# CAN2XG.net
KiCad netlist of a schematic drawn in Altium Designer
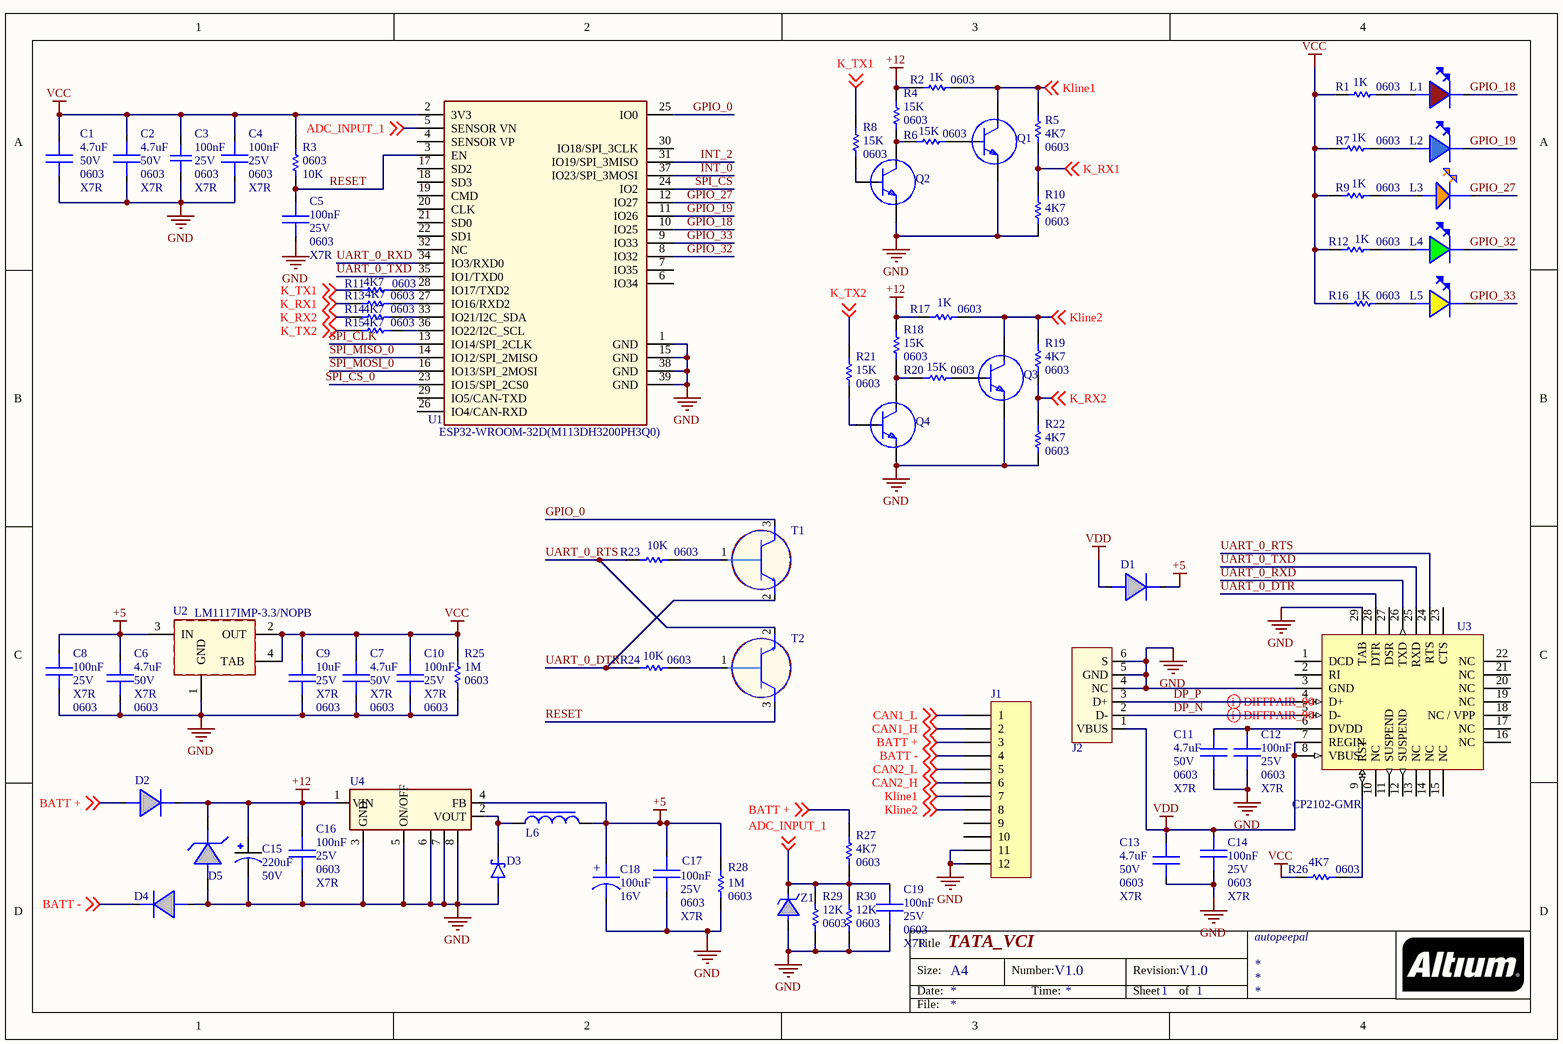
[diagram p0: CAN2XG.SchDoc]

(export (version "E")
  (design (tool "Eeschema 10.0.6"))
  (components
    (comp (ref "C1")
      (value "4.7uF")
      (footprint "CAP-0603")
      (description "CAP CER 4.7uF 50V X7R 0603")
      (fields
        (field (name "VOLTAGE") "50V")
        (field (name "CASE/PACKAGE") "0603")
        (field (name "DIELECTRIC") "X7R")
      )
      (libsource (lib "MyLib") (part "C4.7uF 0603"))
    )
    (comp (ref "C2")
      (value "4.7uF")
      (footprint "CAP-0603")
      (description "CAP CER 4.7uF 50V X7R 0603")
      (fields
        (field (name "VOLTAGE") "50V")
        (field (name "CASE/PACKAGE") "0603")
        (field (name "DIELECTRIC") "X7R")
      )
      (libsource (lib "MyLib") (part "C4.7uF 0603"))
    )
    (comp (ref "C3")
      (value "100nF")
      (footprint "CAP-0603")
      (description "CAP CER 100nF 25V X7R 0603")
      (fields
        (field (name "DIELECTRIC") "X7R")
        (field (name "CASE/PACKAGE") "0603")
        (field (name "VOLTAGE") "25V")
      )
      (libsource (lib "MyLib") (part "C1uF 0603"))
    )
    (comp (ref "C4")
      (value "100nF")
      (footprint "CAP-0603")
      (description "CAP CER 100nF 25V X7R 0603")
      (fields
        (field (name "DIELECTRIC") "X7R")
        (field (name "CASE/PACKAGE") "0603")
        (field (name "VOLTAGE") "25V")
      )
      (libsource (lib "MyLib") (part "C100nF 0603"))
    )
    (comp (ref "C5")
      (value "100nF")
      (footprint "CAP-0603")
      (description "CAP CER 100nF 25V X7R 0603")
      (fields
        (field (name "VOLTAGE") "25V")
        (field (name "CASE/PACKAGE") "0603")
        (field (name "DIELECTRIC") "X7R")
      )
      (libsource (lib "") (part "C1uF 0603_1"))
    )
    (comp (ref "C6")
      (value "4.7uF")
      (footprint "CAP-0603")
      (description "CAP CER 4.7uF 50V X7R 0603")
      (fields
        (field (name "VOLTAGE") "50V")
        (field (name "CASE/PACKAGE") "0603")
        (field (name "DIELECTRIC") "X7R")
      )
      (libsource (lib "MyLib") (part "C4.7uF 0603"))
    )
    (comp (ref "C7")
      (value "4.7uF")
      (footprint "CAP-0603")
      (description "CAP CER 4.7uF 50V X7R 0603")
      (fields
        (field (name "VOLTAGE") "50V")
        (field (name "CASE/PACKAGE") "0603")
        (field (name "DIELECTRIC") "X7R")
      )
      (libsource (lib "MyLib") (part "C4.7uF 0603"))
    )
    (comp (ref "C8")
      (value "100nF")
      (footprint "CAP-0603")
      (description "CAP CER 100nF 25V X7R 0603")
      (fields
        (field (name "VOLTAGE") "25V")
        (field (name "DIELECTRIC") "X7R")
        (field (name "CASE/PACKAGE") "0603")
      )
      (libsource (lib "MyLib") (part "C100nF 0603"))
    )
    (comp (ref "C9")
      (value "10uF")
      (footprint "CAP-0603")
      (description "CAP CER 10uF 25V  0603")
      (fields
        (field (name "VOLTAGE") "25V")
        (field (name "CASE/PACKAGE") "0603")
        (field (name "DIELECTRIC") "X7R")
      )
      (libsource (lib "MyLib") (part "C10uF  0603"))
    )
    (comp (ref "C10")
      (value "100nF")
      (footprint "CAP-0603")
      (description "CAP CER 100nF 25V X7R 0603")
      (fields
        (field (name "CASE/PACKAGE") "0603")
        (field (name "DIELECTRIC") "X7R")
        (field (name "VOLTAGE") "25V")
      )
      (libsource (lib "MyLib") (part "C100nF 0603"))
    )
    (comp (ref "C11")
      (value "4.7uF")
      (footprint "CAP-0603")
      (description "CAP CER 4.7uF 50V X7R 0603")
      (fields
        (field (name "VOLTAGE") "50V")
        (field (name "CASE/PACKAGE") "0603")
        (field (name "DIELECTRIC") "X7R")
      )
      (libsource (lib "MyLib") (part "C4.7uF 0603"))
    )
    (comp (ref "C12")
      (value "100nF")
      (footprint "CAP-0603")
      (description "CAP CER 100nF 25V X7R 0603")
      (fields
        (field (name "VOLTAGE") "25V")
        (field (name "CASE/PACKAGE") "0603")
        (field (name "DIELECTRIC") "X7R")
      )
      (libsource (lib "MyLib") (part "C100nF 0603"))
    )
    (comp (ref "C13")
      (value "4.7uF")
      (footprint "CAP-0603")
      (description "CAP CER 4.7uF 50V X7R 0603")
      (fields
        (field (name "VOLTAGE") "50V")
        (field (name "CASE/PACKAGE") "0603")
        (field (name "DIELECTRIC") "X7R")
      )
      (libsource (lib "MyLib") (part "C4.7uF 0603"))
    )
    (comp (ref "C14")
      (value "100nF")
      (footprint "CAP-0603")
      (description "CAP CER 100nF 25V X7R 0603")
      (fields
        (field (name "VOLTAGE") "25V")
        (field (name "CASE/PACKAGE") "0603")
        (field (name "DIELECTRIC") "X7R")
      )
      (libsource (lib "MyLib") (part "C100nF 0603"))
    )
    (comp (ref "C15")
      (value "220uF")
      (footprint "C200uF 10x10.2")
      (description "220uF 50V 10x10.5mm SMD Electrolytic Capacitor")
      (fields (field (name "VOLTAGE") "50V"))
      (libsource (lib "FotaxLite") (part "C200uF 10x10.2"))
    )
    (comp (ref "C16")
      (value "100nF")
      (footprint "CAP-0603")
      (description "CAP CER 100nF 25V X7R 0603")
      (fields
        (field (name "VOLTAGE") "25V")
        (field (name "CASE/PACKAGE") "0603")
        (field (name "DIELECTRIC") "X7R")
      )
      (libsource (lib "MyLib") (part "C100nF 0603"))
    )
    (comp (ref "C17")
      (value "100nF")
      (footprint "CAP-0603")
      (description "CAP CER 100nF 25V X7R 0603")
      (fields
        (field (name "VOLTAGE") "25V")
        (field (name "CASE/PACKAGE") "0603")
        (field (name "DIELECTRIC") "X7R")
      )
      (libsource (lib "MyLib") (part "C100nF 0603"))
    )
    (comp (ref "C18")
      (value "100uF")
      (footprint "C100uF")
      (description "100uF 16V (107C B3528) Tantalum")
      (fields (field (name "VOLTAGE") "16V"))
      (libsource (lib "MyLib") (part "C100uF"))
    )
    (comp (ref "C19")
      (value "100nF")
      (footprint "CAP-0603")
      (description "CAP CER 100nF 25V X7R 0603")
      (fields
        (field (name "VOLTAGE") "25V")
        (field (name "CASE/PACKAGE") "0603")
        (field (name "DIELECTIC") "X7R")
      )
      (libsource (lib "MyLib") (part "C100nF 0603"))
    )
    (comp (ref "D1")
      (value "~")
      (footprint "DO214")
      (fields (field (name "MANUFACTURER PART NUMBER") "1N4007"))
      (libsource (lib "MyLib") (part "1N4007"))
    )
    (comp (ref "D2")
      (value "~")
      (footprint "DO214")
      (fields (field (name "MAUNFACTURER PART NUMBER") "1N4007"))
      (libsource (lib "MyLib") (part "1N4007"))
    )
    (comp (ref "D3")
      (value "~")
      (footprint "DO214")
      (description "Schottky Diodes & Rectifiers 3.0 Amp 40 Volt")
      (fields (field (name "MANUFACTURER PART NUMBER") "SS34-E3/57T"))
      (libsource (lib "MyLib") (part "SS34-E3/57T"))
    )
    (comp (ref "D4")
      (value "~")
      (footprint "DO214")
      (fields (field (name "MANUFACTURER PART NUMBER") "1N4007"))
      (libsource (lib "MyLib") (part "1N4007"))
    )
    (comp (ref "D5")
      (value "~")
      (footprint "DO214")
      (description "ESD Protection Diodes / TVS Diodes 600W 200V 5% Uni-Directional")
      (fields (field (name "MANUFATURE PART NUMBER") "SMBJ200A"))
      (libsource (lib "MyLib") (part "SMBJ TVS Diode"))
    )
    (comp (ref "J1")
      (value "~")
      (footprint "HDR1X12")
      (description "Header, 12-Pin")
      (libsource (lib "Miscellaneous Connectors") (part "Header 12"))
    )
    (comp (ref "J2")
      (value "~")
      (footprint "1734035-2USB")
      (description "CONN RCPT USB2.0 MINI B SMD R/A")
      (fields (field (name "MANUFACTURER PART NUMBER") "1734035-2"))
      (libsource (lib "MyLib") (part "1734035-2"))
    )
    (comp (ref "L1")
      (value "~")
      (footprint "LEDRED0603")
      (description "LED RED CLEAR 0603 SMD")
      (fields (field (name "MANUFACTURER PART NUMBER") "IN-S63ATR"))
      (libsource (lib "MyLib") (part "IN-S63ATR"))
    )
    (comp (ref "L2")
      (value "~")
      (footprint "LEDBLUE0603")
      (description "LED BLUE CLEAR 0603 SMD")
      (fields (field (name "MANUFACTURER PART NUMBER") "IN-S63AT5B"))
      (libsource (lib "MyLib") (part "IN-S63AT5B"))
    )
    (comp (ref "L3")
      (value "~")
      (footprint "LEDRED0603")
      (description "LED ORANGE CLEAR 0603 SMD")
      (libsource (lib "MyLib") (part "LED_Orange0603"))
    )
    (comp (ref "L4")
      (value "~")
      (footprint "LEDGREEN0603")
      (description "LED GREEN CLEAR 0603 SMD")
      (fields (field (name "MANUFACTURER PART NUMBER") "IN-S63AT5G"))
      (libsource (lib "MyLib") (part "IN-S63AT5G"))
    )
    (comp (ref "L5")
      (value "~")
      (footprint "LEDRED0603")
      (description "LED YELLOW CLEAR 0603 SMD")
      (fields (field (name "MANUFACTURER PART NUMBER") "IN-S63AT5Y"))
      (libsource (lib "MyLib") (part "LED Y 0603"))
    )
    (comp (ref "L6")
      (value "~")
      (footprint "IND-WE-PD 1050-10X10X5MM")
      (description "68uH")
      (libsource (lib "MyLib") (part "L68uH inductor"))
    )
    (comp (ref "Q1")
      (value "~")
      (footprint "SOT95P245X93-3N")
      (description "TRANS NPN 40V 0.6A SOT23-3")
      (fields (field (name "MANUFACTURER PART NUMBER") "MMBT2222ALT1G"))
      (libsource (lib "MyLib") (part "MMBT2222ALT1G"))
    )
    (comp (ref "Q2")
      (value "~")
      (footprint "SOT95P245X93-3N")
      (description "TRANS NPN 40V 0.6A SOT23-3")
      (fields (field (name "MANUFACTURER PART NUMBER") "MMBT2222ALT1G"))
      (libsource (lib "MyLib") (part "MMBT2222ALT1G"))
    )
    (comp (ref "Q3")
      (value "~")
      (footprint "SOT95P245X93-3N")
      (description "TRANS NPN 40V 0.6A SOT23-3")
      (fields (field (name "MANUFACTURER PART NUMBER") "MMBT2222ALT1G"))
      (libsource (lib "MyLib") (part "MMBT2222ALT1G"))
    )
    (comp (ref "Q4")
      (value "~")
      (footprint "SOT95P245X93-3N")
      (description "TRANS NPN 40V 0.6A SOT23-3")
      (fields (field (name "MANUFACTURER PART NUMBER") "MMBT2222ALT1G"))
      (libsource (lib "MyLib") (part "MMBT2222ALT1G"))
    )
    (comp (ref "R1")
      (value "1K")
      (footprint "RESC1608X55X30ML15T15")
      (description "Thick Film Resistor -  1K, 1%, 0603")
      (fields (field (name "CASE/PACKAGE") "0603"))
      (libsource (lib "MyLib") (part "R1K 0603"))
    )
    (comp (ref "R2")
      (value "1K")
      (footprint "RESC1608X55X30ML15T15")
      (description "Thick Film Resistor -  1K ohm, 1%, 0603")
      (fields (field (name "CASE/PACKAGE") "0603"))
      (libsource (lib "MyLib") (part "R1K 0603"))
    )
    (comp (ref "R3")
      (value "10K")
      (footprint "RESC1608X55X30ML15T15")
      (description "Thick Film Resistor -  10Kohm, 1%, 0603")
      (fields (field (name "CASE/PACKAGE") "0603"))
      (libsource (lib "MyLib") (part "R10K 0603"))
    )
    (comp (ref "R4")
      (value "15K")
      (footprint "RESC1608X55X30ML15T15")
      (description "Thick Film Resistor -  15Kohm, 1%, 0603")
      (fields (field (name "CASE/PACKAGE") "0603"))
      (libsource (lib "MyLib") (part "R_15K"))
    )
    (comp (ref "R5")
      (value "4K7")
      (footprint "RESC1608X55X30ML15T15")
      (description "Thick Film Resistor -  4K7 ohm, 1%, 0603")
      (fields (field (name "CASE/PACKAGE") "0603"))
      (libsource (lib "MyLib") (part "R_4k7"))
    )
    (comp (ref "R6")
      (value "15K")
      (footprint "RESC1608X55X30ML15T15")
      (description "Thick Film Resistor -  15Kohm, 1%, 0603")
      (fields (field (name "CASE/PACKAGE") "0603"))
      (libsource (lib "MyLib") (part "R_15K"))
    )
    (comp (ref "R7")
      (value "1K")
      (footprint "RESC1608X55X30ML15T15")
      (description "Thick Film Resistor -  1K, 1%, 0603")
      (fields (field (name "CASE/PACKAGE") "0603"))
      (libsource (lib "MyLib") (part "R1K 0603"))
    )
    (comp (ref "R8")
      (value "15K")
      (footprint "RESC1608X55X30ML15T15")
      (description "Thick Film Resistor -  15Kohm, 1%, 0603")
      (fields (field (name "CASE/PACKAGE") "0603"))
      (libsource (lib "MyLib") (part "R_15K"))
    )
    (comp (ref "R9")
      (value "1K")
      (footprint "RESC1608X55X30ML15T15")
      (description "Thick Film Resistor -  1K, 1%, 0603")
      (fields (field (name "CASE/PACKAGE") "0603"))
      (libsource (lib "MyLib") (part "R1K 0603"))
    )
    (comp (ref "R10")
      (value "4K7")
      (footprint "RESC1608X55X30ML15T15")
      (description "Thick Film Resistor -  4K7 ohm, 1%, 0603")
      (fields (field (name "CASE/PACKAGE") "0603"))
      (libsource (lib "MyLib") (part "R_4k7"))
    )
    (comp (ref "R11")
      (value "4K7")
      (footprint "RESC1608X55X30ML15T15")
      (description "Thick Film Resistor -  4K7, 1%, 0603")
      (fields (field (name "CASE/PACKAGE") "0603"))
      (libsource (lib "MyLib") (part "R_4k7"))
    )
    (comp (ref "R12")
      (value "1K")
      (footprint "RESC1608X55X30ML15T15")
      (description "Thick Film Resistor -  1K, 1%, 0603")
      (fields (field (name "CASE/PACKAGE") "0603"))
      (libsource (lib "MyLib") (part "R1K 0603"))
    )
    (comp (ref "R13")
      (value "4K7")
      (footprint "RESC1608X55X30ML15T15")
      (description "Thick Film Resistor -  4K7, 1%, 0603")
      (fields (field (name "CASE/PACKAGE") "0603"))
      (libsource (lib "MyLib") (part "R_4k7"))
    )
    (comp (ref "R14")
      (value "4K7")
      (footprint "RESC1608X55X30ML15T15")
      (description "Thick Film Resistor -  4K7, 1%, 0603")
      (fields (field (name "CASE/PACKAGE") "0603"))
      (libsource (lib "MyLib") (part "R_4k7"))
    )
    (comp (ref "R15")
      (value "4K7")
      (footprint "RESC1608X55X30ML15T15")
      (description "Thick Film Resistor -  4K7, 1%, 0603")
      (fields (field (name "CASE/PACKAGE") "0603"))
      (libsource (lib "MyLib") (part "R_4k7"))
    )
    (comp (ref "R16")
      (value "1K")
      (footprint "RESC1608X55X30ML15T15")
      (description "Thick Film Resistor -  1K, 1%, 0603")
      (fields (field (name "CASE/PACKAGE") "0603"))
      (libsource (lib "MyLib") (part "R1K 0603"))
    )
    (comp (ref "R17")
      (value "1K")
      (footprint "RESC1608X55X30ML15T15")
      (description "Thick Film Resistor -  1K ohm, 1%, 0603")
      (fields (field (name "CASE/PACKAGE") "0603"))
      (libsource (lib "MyLib") (part "R1K 0603"))
    )
    (comp (ref "R18")
      (value "15K")
      (footprint "RESC1608X55X30ML15T15")
      (description "Thick Film Resistor -  15Kohm, 1%, 0603")
      (fields (field (name "CASE/PACKAGE") "0603"))
      (libsource (lib "MyLib") (part "R_15K"))
    )
    (comp (ref "R19")
      (value "4K7")
      (footprint "RESC1608X55X30ML15T15")
      (description "Thick Film Resistor -  4K7ohm, 1%, 0603")
      (fields (field (name "CASE/PACKAGE") "0603"))
      (libsource (lib "MyLib") (part "R_4k7"))
    )
    (comp (ref "R20")
      (value "15K")
      (footprint "RESC1608X55X30ML15T15")
      (description "Thick Film Resistor -  15Kohm, 1%, 0603")
      (fields (field (name "CASE/PACKAGE") "0603"))
      (libsource (lib "MyLib") (part "R_15K"))
    )
    (comp (ref "R21")
      (value "15K")
      (footprint "RESC1608X55X30ML15T15")
      (description "Thick Film Resistor -  15Kohm, 1%, 0603")
      (fields (field (name "CASE/PACKAGE") "0603"))
      (libsource (lib "MyLib") (part "R_15K"))
    )
    (comp (ref "R22")
      (value "4K7")
      (footprint "RESC1608X55X30ML15T15")
      (description "Thick Film Resistor -  4K7ohm, 1%, 0603")
      (fields (field (name "CASE/PACKAGE") "0603"))
      (libsource (lib "MyLib") (part "R_4k7"))
    )
    (comp (ref "R23")
      (value "10K")
      (footprint "RESC1608X55X30ML15T15")
      (description "Thick Film Resistor -  10K, 1%, 0603")
      (fields (field (name "CASE/PACKAGE") "0603"))
      (libsource (lib "MyLib") (part "R10K 0603"))
    )
    (comp (ref "R24")
      (value "10K")
      (footprint "RESC1608X55X30ML15T15")
      (description "Thick Film Resistor -  10K, 1%, 0603")
      (fields (field (name "CASE/PACAKE") "0603"))
      (libsource (lib "MyLib") (part "R10K 0603"))
    )
    (comp (ref "R25")
      (value "1M")
      (footprint "RESC1608X55X30ML15T15")
      (description "Thick Film Resistor -  10M, 1%, 0603")
      (fields (field (name "CASE/PACKAGE") "0603"))
      (libsource (lib "MyLib") (part "R1MOhm 0603"))
    )
    (comp (ref "R26")
      (value "4K7")
      (footprint "RESC1608X55X30ML15T15")
      (description "Thick Film Resistor -  4K7 ohm, 1%, 0603")
      (fields (field (name "CASE/PACKAGE") "0603"))
      (libsource (lib "") (part "R_4k7_1"))
    )
    (comp (ref "R27")
      (value "4K7")
      (footprint "RESC1608X55X30ML15T15")
      (description "Thick Film Resistor -  4K7 ohm, 1%, 0603")
      (fields (field (name "CASE/PACKAGE") "0603"))
      (libsource (lib "MyLib") (part "R_47K"))
    )
    (comp (ref "R28")
      (value "1M")
      (footprint "RESC1608X55X30ML15T15")
      (description "Thick Film Resistor -  10M, 1%, 0603")
      (fields (field (name "CASE/PACKAGE") "0603"))
      (libsource (lib "MyLib") (part "R1MOhm 0603"))
    )
    (comp (ref "R29")
      (value "12K")
      (footprint "RESC1608X55X30ML15T15")
      (description "Thick Film Resistor -  12K ohm, 1%, 0603")
      (fields (field (name "CASE/PACKAGE") "0603"))
      (libsource (lib "MyLib") (part "R12K 0603"))
    )
    (comp (ref "R30")
      (value "12K")
      (footprint "RESC1608X55X30ML15T15")
      (description "Thick Film Resistor -  12K ohm, 1%, 0603")
      (fields (field (name "CASE/PACKAGE") "0603"))
      (libsource (lib "MyLib") (part "R12K 0603"))
    )
    (comp (ref "T1")
      (value "~")
      (footprint "2N2222")
      (description "2TRANS NPN 30V 0.6A SOT23-3")
      (fields (field (name "MANUFACTURER PART NUMBER") "MMBT2222"))
      (libsource (lib "") (part "MMBT2222_1"))
    )
    (comp (ref "T2")
      (value "~")
      (footprint "2N2222")
      (description "2TRANS NPN 30V 0.6A SOT23-3")
      (fields (field (name "MANUFACTURER PART NUMBER") "MMBT2222"))
      (libsource (lib "MyLib") (part "MMBT2222"))
    )
    (comp (ref "U1")
      (value "~")
      (footprint "Espressif_Systems_ESP32-WROOM-32D_MFG")
      (description "WiFi Modules (802.11) SMD Module, ESP32-D0WD, 32Mbits SPI 4MB flash, UART mode, PCB antenna")
      (fields (field (name "MANUFACTURER PART NUMBER") "ESP32-WROOM-32D(M113DH3200PH3Q0)"))
      (libsource (lib "MyLib") (part "ESP32-WROOM-32D(M113DH3200PH3Q0)"))
    )
    (comp (ref "U2")
      (value "~")
      (footprint "SOT223")
      (description "LDO Voltage Regulators 800MA LDO LINEAR REG")
      (fields (field (name "MANUFACTURER PART NUMBER") "LM1117IMP-3.3/NOPB"))
      (libsource (lib "MyLib") (part "LM1117IMP-3.3/NOPB"))
    )
    (comp (ref "U3")
      (value "~")
      (footprint "QFN50P500X500X100_HS-29N")
      (description "USB-to-UART 1-CH 640byte FIFO 3.3V Automotive 28-Pin QFN EP T/R")
      (fields (field (name "MANUFACTURER PART NUMBER") "CP2102-GMR"))
      (libsource (lib "MyLib") (part "CP2102-GMR"))
    )
    (comp (ref "U4")
      (value "~")
      (footprint "to-263")
      (description "Switching Voltage Regulators 150 KHZ 3A STEP-DOWN VLTG REG")
      (fields (field (name "MANUFACTURER PART NUMBER") "LM2596S-5.0/NOPB"))
      (libsource (lib "MyLib") (part "LM2596S-5.0/NOPB"))
    )
    (comp (ref "Z1")
      (value "~")
      (footprint "SOD80")
      (description "Zener Diode 5.1V\r\n500mW\r\n5% Tolerance\r\nSMD Equivalent of BZX55C5V1")
      (fields (field (name "VOLTAGE") "5.1V"))
      (libsource (lib "MyLib") (part "Zener5.1V"))
    )
  )
  (nets
    (net (code "1") (name "+5") (class "Default")
      (node (ref "C17") (pin "2") (pinfunction "2_2") (pintype "passive"))
      (node (ref "C18") (pin "1") (pinfunction "+_1") (pintype "passive"))
      (node (ref "C6") (pin "2") (pinfunction "2_2") (pintype "passive"))
      (node (ref "C8") (pin "2") (pinfunction "2_2") (pintype "passive"))
      (node (ref "D1") (pin "1") (pinfunction "K_1") (pintype "passive"))
      (node (ref "L6") (pin "2") (pinfunction "2_2") (pintype "passive"))
      (node (ref "R28") (pin "2") (pinfunction "2_2") (pintype "passive"))
      (node (ref "U2") (pin "3") (pinfunction "IN_3") (pintype "power_in"))
      (node (ref "U4") (pin "4") (pinfunction "FB_4") (pintype "passive"))
    )
    (net (code "2") (name "+12") (class "Default")
      (node (ref "C15") (pin "1") (pinfunction "1_1") (pintype "passive"))
      (node (ref "C16") (pin "2") (pinfunction "2_2") (pintype "passive"))
      (node (ref "D2") (pin "1") (pinfunction "K_1") (pintype "passive"))
      (node (ref "D5") (pin "1") (pinfunction "K_1") (pintype "passive"))
      (node (ref "R17") (pin "2") (pinfunction "2_2") (pintype "passive"))
      (node (ref "R18") (pin "2") (pinfunction "2_2") (pintype "passive"))
      (node (ref "R2") (pin "2") (pinfunction "2_2") (pintype "passive"))
      (node (ref "R4") (pin "2") (pinfunction "2_2") (pintype "passive"))
      (node (ref "U4") (pin "1") (pinfunction "VIN_1") (pintype "passive"))
    )
    (net (code "3") (name "/DP_N") (class "Default")
      (node (ref "J2") (pin "2") (pinfunction "D-_2") (pintype "passive"))
      (node (ref "U3") (pin "5") (pinfunction "D-_5") (pintype "bidirectional"))
    )
    (net (code "4") (name "/DP_P") (class "Default")
      (node (ref "J2") (pin "3") (pinfunction "D+_3") (pintype "passive"))
      (node (ref "U3") (pin "4") (pinfunction "D+_4") (pintype "bidirectional"))
    )
    (net (code "5") (name "/GPIO_0") (class "Default")
      (node (ref "T1") (pin "3") (pinfunction "C_3") (pintype "passive"))
      (node (ref "U1") (pin "25") (pinfunction "IO0_25") (pintype "passive"))
    )
    (net (code "6") (name "/GPIO_18") (class "Default")
      (node (ref "L1") (pin "1") (pinfunction "C_1") (pintype "passive"))
      (node (ref "U1") (pin "10") (pinfunction "IO25_10") (pintype "passive"))
    )
    (net (code "7") (name "/GPIO_19") (class "Default")
      (node (ref "L2") (pin "1") (pinfunction "C_1") (pintype "passive"))
      (node (ref "U1") (pin "11") (pinfunction "IO26_11") (pintype "passive"))
    )
    (net (code "8") (name "/GPIO_27") (class "Default")
      (node (ref "L3") (pin "1") (pinfunction "C_1") (pintype "passive"))
      (node (ref "U1") (pin "12") (pinfunction "IO27_12") (pintype "passive"))
    )
    (net (code "9") (name "/GPIO_32") (class "Default")
      (node (ref "L4") (pin "1") (pinfunction "C_1") (pintype "passive"))
      (node (ref "U1") (pin "8") (pinfunction "IO32_8") (pintype "passive"))
    )
    (net (code "10") (name "/GPIO_33") (class "Default")
      (node (ref "L5") (pin "1") (pinfunction "C_1") (pintype "passive"))
      (node (ref "U1") (pin "9") (pinfunction "IO33_9") (pintype "passive"))
    )
    (net (code "11") (name "/INT_0") (class "Default")
      (node (ref "U1") (pin "37") (pinfunction "IO23/SPI_3MOSI_37") (pintype "passive"))
    )
    (net (code "12") (name "/INT_2") (class "Default")
      (node (ref "U1") (pin "31") (pinfunction "IO19/SPI_3MISO_31") (pintype "passive"))
    )
    (net (code "13") (name "/RESET") (class "Default")
      (node (ref "C5") (pin "2") (pinfunction "2_2") (pintype "passive"))
      (node (ref "R3") (pin "1") (pinfunction "1_1") (pintype "passive"))
      (node (ref "T2") (pin "3") (pinfunction "C_3") (pintype "passive"))
      (node (ref "U1") (pin "3") (pinfunction "EN_3") (pintype "passive"))
    )
    (net (code "14") (name "/SPI_CLK") (class "Default")
      (node (ref "U1") (pin "13") (pinfunction "IO14/SPI_2CLK_13") (pintype "passive"))
    )
    (net (code "15") (name "/SPI_CS") (class "Default")
      (node (ref "U1") (pin "24") (pinfunction "IO2_24") (pintype "passive"))
    )
    (net (code "16") (name "/SPI_CS_0") (class "Default")
      (node (ref "U1") (pin "23") (pinfunction "IO15/SPI_2CS0_23") (pintype "passive"))
    )
    (net (code "17") (name "/SPI_MISO_0") (class "Default")
      (node (ref "U1") (pin "14") (pinfunction "IO12/SPI_2MISO_14") (pintype "passive"))
    )
    (net (code "18") (name "/SPI_MOSI_0") (class "Default")
      (node (ref "U1") (pin "16") (pinfunction "IO13/SPI_2MOSI_16") (pintype "passive"))
    )
    (net (code "19") (name "/UART_0_DTR") (class "Default")
      (node (ref "R24") (pin "2") (pinfunction "2_2") (pintype "passive"))
      (node (ref "T1") (pin "2") (pinfunction "E_2") (pintype "passive"))
      (node (ref "U3") (pin "28") (pinfunction "DTR_28") (pintype "passive"))
    )
    (net (code "20") (name "/UART_0_RTS") (class "Default")
      (node (ref "R23") (pin "2") (pinfunction "2_2") (pintype "passive"))
      (node (ref "T2") (pin "2") (pinfunction "E_2") (pintype "passive"))
      (node (ref "U3") (pin "24") (pinfunction "RTS_24") (pintype "passive"))
    )
    (net (code "21") (name "/UART_0_RXD") (class "Default")
      (node (ref "U1") (pin "34") (pinfunction "IO3/RXD0_34") (pintype "passive"))
      (node (ref "U3") (pin "26") (pinfunction "TXD_26") (pintype "output"))
    )
    (net (code "22") (name "/UART_0_TXD") (class "Default")
      (node (ref "U1") (pin "35") (pinfunction "IO1/TXD0_35") (pintype "passive"))
      (node (ref "U3") (pin "25") (pinfunction "RXD_25") (pintype "passive"))
    )
    (net (code "23") (name "ADC_INPUT_1") (class "Default")
      (node (ref "C19") (pin "2") (pinfunction "2_2") (pintype "passive"))
      (node (ref "R27") (pin "1") (pinfunction "1_1") (pintype "passive"))
      (node (ref "R29") (pin "2") (pinfunction "2_2") (pintype "passive"))
      (node (ref "R30") (pin "2") (pinfunction "2_2") (pintype "passive"))
      (node (ref "U1") (pin "5") (pinfunction "SENSOR_VN_5") (pintype "passive"))
      (node (ref "Z1") (pin "1") (pinfunction "K_1") (pintype "passive"))
    )
    (net (code "24") (name "BATT +") (class "Default")
      (node (ref "D2") (pin "2") (pinfunction "A_2") (pintype "passive"))
      (node (ref "J1") (pin "3") (pinfunction "3_3") (pintype "passive"))
      (node (ref "R27") (pin "2") (pinfunction "2_2") (pintype "passive"))
    )
    (net (code "25") (name "BATT -") (class "Default")
      (node (ref "D4") (pin "1") (pinfunction "K_1") (pintype "passive"))
      (node (ref "J1") (pin "4") (pinfunction "4_4") (pintype "passive"))
    )
    (net (code "26") (name "CAN1_H") (class "Default")
      (node (ref "J1") (pin "2") (pinfunction "2_2") (pintype "passive"))
    )
    (net (code "27") (name "CAN1_L") (class "Default")
      (node (ref "J1") (pin "1") (pinfunction "1_1") (pintype "passive"))
    )
    (net (code "28") (name "CAN2_H") (class "Default")
      (node (ref "J1") (pin "6") (pinfunction "6_6") (pintype "passive"))
    )
    (net (code "29") (name "CAN2_L") (class "Default")
      (node (ref "J1") (pin "5") (pinfunction "5_5") (pintype "passive"))
    )
    (net (code "30") (name "GND") (class "Default")
      (node (ref "C1") (pin "1") (pinfunction "1_1") (pintype "passive"))
      (node (ref "C10") (pin "1") (pinfunction "1_1") (pintype "passive"))
      (node (ref "C11") (pin "1") (pinfunction "1_1") (pintype "passive"))
      (node (ref "C12") (pin "1") (pinfunction "1_1") (pintype "passive"))
      (node (ref "C13") (pin "1") (pinfunction "1_1") (pintype "passive"))
      (node (ref "C14") (pin "1") (pinfunction "1_1") (pintype "passive"))
      (node (ref "C15") (pin "2") (pinfunction "2_2") (pintype "passive"))
      (node (ref "C16") (pin "1") (pinfunction "1_1") (pintype "passive"))
      (node (ref "C17") (pin "1") (pinfunction "1_1") (pintype "passive"))
      (node (ref "C18") (pin "2") (pinfunction "-_2") (pintype "passive"))
      (node (ref "C19") (pin "1") (pinfunction "1_1") (pintype "passive"))
      (node (ref "C2") (pin "1") (pinfunction "1_1") (pintype "passive"))
      (node (ref "C3") (pin "1") (pinfunction "1_1") (pintype "passive"))
      (node (ref "C4") (pin "1") (pinfunction "1_1") (pintype "passive"))
      (node (ref "C5") (pin "1") (pinfunction "1_1") (pintype "passive"))
      (node (ref "C6") (pin "1") (pinfunction "1_1") (pintype "passive"))
      (node (ref "C7") (pin "1") (pinfunction "1_1") (pintype "passive"))
      (node (ref "C8") (pin "1") (pinfunction "1_1") (pintype "passive"))
      (node (ref "C9") (pin "1") (pinfunction "1_1") (pintype "passive"))
      (node (ref "D3") (pin "2") (pinfunction "2_2") (pintype "passive"))
      (node (ref "D4") (pin "2") (pinfunction "A_2") (pintype "passive"))
      (node (ref "D5") (pin "2") (pinfunction "A_2") (pintype "passive"))
      (node (ref "J1") (pin "11") (pinfunction "11_11") (pintype "passive"))
      (node (ref "J1") (pin "12") (pinfunction "12_12") (pintype "passive"))
      (node (ref "J2") (pin "4") (pinfunction "NC_4") (pintype "passive"))
      (node (ref "J2") (pin "5") (pinfunction "GND_5") (pintype "passive"))
      (node (ref "J2") (pin "6") (pinfunction "S_6") (pintype "passive"))
      (node (ref "Q1") (pin "2") (pinfunction "E_2") (pintype "passive"))
      (node (ref "Q2") (pin "2") (pinfunction "E_2") (pintype "passive"))
      (node (ref "Q3") (pin "2") (pinfunction "E_2") (pintype "passive"))
      (node (ref "Q4") (pin "2") (pinfunction "E_2") (pintype "passive"))
      (node (ref "R10") (pin "1") (pinfunction "1_1") (pintype "passive"))
      (node (ref "R22") (pin "1") (pinfunction "1_1") (pintype "passive"))
      (node (ref "R25") (pin "1") (pinfunction "1_1") (pintype "passive"))
      (node (ref "R28") (pin "1") (pinfunction "1_1") (pintype "passive"))
      (node (ref "R29") (pin "1") (pinfunction "1_1") (pintype "passive"))
      (node (ref "R30") (pin "1") (pinfunction "1_1") (pintype "passive"))
      (node (ref "U1") (pin "1") (pinfunction "GND_1") (pintype "passive"))
      (node (ref "U1") (pin "15") (pinfunction "GND_15") (pintype "passive"))
      (node (ref "U1") (pin "38") (pinfunction "GND_38") (pintype "passive"))
      (node (ref "U1") (pin "39") (pinfunction "GND_39") (pintype "passive"))
      (node (ref "U2") (pin "1") (pinfunction "GND_1") (pintype "power_in"))
      (node (ref "U3") (pin "29") (pinfunction "TAB_29") (pintype "power_in"))
      (node (ref "U3") (pin "3") (pinfunction "GND_3") (pintype "power_in"))
      (node (ref "U4") (pin "3") (pinfunction "GND_3") (pintype "passive"))
      (node (ref "U4") (pin "5") (pinfunction "ON/OFF_5") (pintype "passive"))
      (node (ref "U4") (pin "6") (pinfunction "6_6") (pintype "passive"))
      (node (ref "U4") (pin "7") (pinfunction "7_7") (pintype "passive"))
      (node (ref "U4") (pin "8") (pinfunction "8_8") (pintype "passive"))
      (node (ref "Z1") (pin "2") (pinfunction "A_2") (pintype "passive"))
    )
    (net (code "31") (name "K_RX1") (class "Default")
      (node (ref "R10") (pin "2") (pinfunction "2_2") (pintype "passive"))
      (node (ref "R13") (pin "1") (pinfunction "1_1") (pintype "passive"))
      (node (ref "R5") (pin "1") (pinfunction "1_1") (pintype "passive"))
    )
    (net (code "32") (name "K_RX2") (class "Default")
      (node (ref "R14") (pin "1") (pinfunction "1_1") (pintype "passive"))
      (node (ref "R19") (pin "1") (pinfunction "1_1") (pintype "passive"))
      (node (ref "R22") (pin "2") (pinfunction "2_2") (pintype "passive"))
    )
    (net (code "33") (name "K_TX1") (class "Default")
      (node (ref "R11") (pin "1") (pinfunction "1_1") (pintype "passive"))
      (node (ref "R8") (pin "2") (pinfunction "2_2") (pintype "passive"))
    )
    (net (code "34") (name "K_TX2") (class "Default")
      (node (ref "R15") (pin "1") (pinfunction "1_1") (pintype "passive"))
      (node (ref "R21") (pin "2") (pinfunction "2_2") (pintype "passive"))
    )
    (net (code "35") (name "Kline1") (class "Default")
      (node (ref "J1") (pin "7") (pinfunction "7_7") (pintype "passive"))
      (node (ref "Q1") (pin "3") (pinfunction "C_3") (pintype "passive"))
      (node (ref "R2") (pin "1") (pinfunction "1_1") (pintype "passive"))
      (node (ref "R5") (pin "2") (pinfunction "2_2") (pintype "passive"))
    )
    (net (code "36") (name "Kline2") (class "Default")
      (node (ref "J1") (pin "8") (pinfunction "8_8") (pintype "passive"))
      (node (ref "Q3") (pin "3") (pinfunction "C_3") (pintype "passive"))
      (node (ref "R17") (pin "1") (pinfunction "1_1") (pintype "passive"))
      (node (ref "R19") (pin "2") (pinfunction "2_2") (pintype "passive"))
    )
    (net (code "37") (name "Net-(L1-A)") (class "Default")
      (node (ref "L1") (pin "2") (pinfunction "A_2") (pintype "passive"))
      (node (ref "R1") (pin "2") (pinfunction "2_2") (pintype "passive"))
    )
    (net (code "38") (name "Net-(L2-A)") (class "Default")
      (node (ref "L2") (pin "2") (pinfunction "A_2") (pintype "passive"))
      (node (ref "R7") (pin "2") (pinfunction "2_2") (pintype "passive"))
    )
    (net (code "39") (name "Net-(L3-A)") (class "Default")
      (node (ref "L3") (pin "2") (pinfunction "A_2") (pintype "passive"))
      (node (ref "R9") (pin "2") (pinfunction "2_2") (pintype "passive"))
    )
    (net (code "40") (name "Net-(L4-A)") (class "Default")
      (node (ref "L4") (pin "2") (pinfunction "A_2") (pintype "passive"))
      (node (ref "R12") (pin "2") (pinfunction "2_2") (pintype "passive"))
    )
    (net (code "41") (name "Net-(L5-A)") (class "Default")
      (node (ref "L5") (pin "2") (pinfunction "A_2") (pintype "passive"))
      (node (ref "R16") (pin "2") (pinfunction "2_2") (pintype "passive"))
    )
    (net (code "42") (name "Net-(Q1-B)") (class "Default")
      (node (ref "Q1") (pin "1") (pinfunction "B_1") (pintype "passive"))
      (node (ref "R6") (pin "1") (pinfunction "1_1") (pintype "passive"))
    )
    (net (code "43") (name "Net-(Q2-B)") (class "Default")
      (node (ref "Q2") (pin "1") (pinfunction "B_1") (pintype "passive"))
      (node (ref "R8") (pin "1") (pinfunction "1_1") (pintype "passive"))
    )
    (net (code "44") (name "Net-(Q2-C)") (class "Default")
      (node (ref "Q2") (pin "3") (pinfunction "C_3") (pintype "passive"))
      (node (ref "R4") (pin "1") (pinfunction "1_1") (pintype "passive"))
      (node (ref "R6") (pin "2") (pinfunction "2_2") (pintype "passive"))
    )
    (net (code "45") (name "Net-(Q3-B)") (class "Default")
      (node (ref "Q3") (pin "1") (pinfunction "B_1") (pintype "passive"))
      (node (ref "R20") (pin "1") (pinfunction "1_1") (pintype "passive"))
    )
    (net (code "46") (name "Net-(Q4-B)") (class "Default")
      (node (ref "Q4") (pin "1") (pinfunction "B_1") (pintype "passive"))
      (node (ref "R21") (pin "1") (pinfunction "1_1") (pintype "passive"))
    )
    (net (code "47") (name "Net-(Q4-C)") (class "Default")
      (node (ref "Q4") (pin "3") (pinfunction "C_3") (pintype "passive"))
      (node (ref "R18") (pin "1") (pinfunction "1_1") (pintype "passive"))
      (node (ref "R20") (pin "2") (pinfunction "2_2") (pintype "passive"))
    )
    (net (code "48") (name "Net-(T1-B)") (class "Default")
      (node (ref "R23") (pin "1") (pinfunction "1_1") (pintype "passive"))
      (node (ref "T1") (pin "1") (pinfunction "B_1") (pintype "passive"))
    )
    (net (code "49") (name "Net-(T2-B)") (class "Default")
      (node (ref "R24") (pin "1") (pinfunction "1_1") (pintype "passive"))
      (node (ref "T2") (pin "1") (pinfunction "B_1") (pintype "passive"))
    )
    (net (code "50") (name "Net-(U1-IO16{slash}RXD2)") (class "Default")
      (node (ref "R13") (pin "2") (pinfunction "2_2") (pintype "passive"))
      (node (ref "U1") (pin "27") (pinfunction "IO16/RXD2_27") (pintype "passive"))
    )
    (net (code "51") (name "Net-(U1-IO17{slash}TXD2)") (class "Default")
      (node (ref "R11") (pin "2") (pinfunction "2_2") (pintype "passive"))
      (node (ref "U1") (pin "28") (pinfunction "IO17/TXD2_28") (pintype "passive"))
    )
    (net (code "52") (name "Net-(U1-IO21{slash}I2C_SDA)") (class "Default")
      (node (ref "R14") (pin "2") (pinfunction "2_2") (pintype "passive"))
      (node (ref "U1") (pin "33") (pinfunction "IO21/I2C_SDA_33") (pintype "passive"))
    )
    (net (code "53") (name "Net-(U1-IO22{slash}I2C_SCL)") (class "Default")
      (node (ref "R15") (pin "2") (pinfunction "2_2") (pintype "passive"))
      (node (ref "U1") (pin "36") (pinfunction "IO22/I2C_SCL_36") (pintype "passive"))
    )
    (net (code "54") (name "Net-(U3-DVDD)") (class "Default")
      (node (ref "C11") (pin "2") (pinfunction "2_2") (pintype "passive"))
      (node (ref "C12") (pin "2") (pinfunction "2_2") (pintype "passive"))
      (node (ref "U3") (pin "6") (pinfunction "DVDD_6") (pintype "power_in"))
    )
    (net (code "55") (name "Net-(U3-RST)") (class "Default")
      (node (ref "R26") (pin "2") (pinfunction "2_2") (pintype "passive"))
      (node (ref "U3") (pin "9") (pinfunction "RST_9") (pintype "bidirectional"))
    )
    (net (code "56") (name "Net-(U4-VOUT)") (class "Default")
      (node (ref "D3") (pin "1") (pinfunction "1_1") (pintype "passive"))
      (node (ref "L6") (pin "1") (pinfunction "1_1") (pintype "passive"))
      (node (ref "U4") (pin "2") (pinfunction "VOUT_2") (pintype "passive"))
    )
    (net (code "57") (name "VCC") (class "Default")
      (node (ref "C1") (pin "2") (pinfunction "2_2") (pintype "passive"))
      (node (ref "C10") (pin "2") (pinfunction "2_2") (pintype "passive"))
      (node (ref "C2") (pin "2") (pinfunction "2_2") (pintype "passive"))
      (node (ref "C3") (pin "2") (pinfunction "2_2") (pintype "passive"))
      (node (ref "C4") (pin "2") (pinfunction "2_2") (pintype "passive"))
      (node (ref "C7") (pin "2") (pinfunction "2_2") (pintype "passive"))
      (node (ref "C9") (pin "2") (pinfunction "2_2") (pintype "passive"))
      (node (ref "R1") (pin "1") (pinfunction "1_1") (pintype "passive"))
      (node (ref "R12") (pin "1") (pinfunction "1_1") (pintype "passive"))
      (node (ref "R16") (pin "1") (pinfunction "1_1") (pintype "passive"))
      (node (ref "R25") (pin "2") (pinfunction "2_2") (pintype "passive"))
      (node (ref "R26") (pin "1") (pinfunction "1_1") (pintype "passive"))
      (node (ref "R3") (pin "2") (pinfunction "2_2") (pintype "passive"))
      (node (ref "R7") (pin "1") (pinfunction "1_1") (pintype "passive"))
      (node (ref "R9") (pin "1") (pinfunction "1_1") (pintype "passive"))
      (node (ref "U1") (pin "2") (pinfunction "3V3_2") (pintype "passive"))
      (node (ref "U2") (pin "2") (pinfunction "OUT_2") (pintype "power_in"))
      (node (ref "U2") (pin "4") (pinfunction "TAB_4") (pintype "power_in"))
    )
    (net (code "58") (name "VDD") (class "Default")
      (node (ref "C13") (pin "2") (pinfunction "2_2") (pintype "passive"))
      (node (ref "C14") (pin "2") (pinfunction "2_2") (pintype "passive"))
      (node (ref "D1") (pin "2") (pinfunction "A_2") (pintype "passive"))
      (node (ref "J2") (pin "1") (pinfunction "VBUS_1") (pintype "passive"))
      (node (ref "U3") (pin "7") (pinfunction "REGIN_7") (pintype "power_in"))
      (node (ref "U3") (pin "8") (pinfunction "VBUS_8") (pintype "input"))
    )
    (net (code "59") (name "unconnected-(J1-Pad9)") (class "Default")
      (node (ref "J1") (pin "9") (pinfunction "9_9") (pintype "passive"))
    )
    (net (code "60") (name "unconnected-(J1-Pad10)") (class "Default")
      (node (ref "J1") (pin "10") (pinfunction "10_10") (pintype "passive"))
    )
    (net (code "61") (name "unconnected-(U1-CLK-Pad20)") (class "Default")
      (node (ref "U1") (pin "20") (pinfunction "CLK_20") (pintype "passive"))
    )
    (net (code "62") (name "unconnected-(U1-CMD-Pad19)") (class "Default")
      (node (ref "U1") (pin "19") (pinfunction "CMD_19") (pintype "passive"))
    )
    (net (code "63") (name "unconnected-(U1-IO4{slash}CAN-RXD-Pad26)") (class "Default")
      (node (ref "U1") (pin "26") (pinfunction "IO4/CAN-RXD_26") (pintype "passive"))
    )
    (net (code "64") (name "unconnected-(U1-IO5{slash}CAN-TXD-Pad29)") (class "Default")
      (node (ref "U1") (pin "29") (pinfunction "IO5/CAN-TXD_29") (pintype "passive"))
    )
    (net (code "65") (name "unconnected-(U1-IO18{slash}SPI_3CLK-Pad30)") (class "Default")
      (node (ref "U1") (pin "30") (pinfunction "IO18/SPI_3CLK_30") (pintype "passive"))
    )
    (net (code "66") (name "unconnected-(U1-IO34-Pad6)") (class "Default")
      (node (ref "U1") (pin "6") (pinfunction "IO34_6") (pintype "passive"))
    )
    (net (code "67") (name "unconnected-(U1-IO35-Pad7)") (class "Default")
      (node (ref "U1") (pin "7") (pinfunction "IO35_7") (pintype "passive"))
    )
    (net (code "68") (name "unconnected-(U1-NC-Pad32)") (class "Default")
      (node (ref "U1") (pin "32") (pinfunction "NC_32") (pintype "passive"))
    )
    (net (code "69") (name "unconnected-(U1-SD0-Pad21)") (class "Default")
      (node (ref "U1") (pin "21") (pinfunction "SD0_21") (pintype "passive"))
    )
    (net (code "70") (name "unconnected-(U1-SD1-Pad22)") (class "Default")
      (node (ref "U1") (pin "22") (pinfunction "SD1_22") (pintype "passive"))
    )
    (net (code "71") (name "unconnected-(U1-SD2-Pad17)") (class "Default")
      (node (ref "U1") (pin "17") (pinfunction "SD2_17") (pintype "passive"))
    )
    (net (code "72") (name "unconnected-(U1-SD3-Pad18)") (class "Default")
      (node (ref "U1") (pin "18") (pinfunction "SD3_18") (pintype "passive"))
    )
    (net (code "73") (name "unconnected-(U1-SENSOR_VP-Pad4)") (class "Default")
      (node (ref "U1") (pin "4") (pinfunction "SENSOR_VP_4") (pintype "passive"))
    )
    (net (code "74") (name "unconnected-(U3-CTS-Pad23)") (class "Default")
      (node (ref "U3") (pin "23") (pinfunction "CTS_23") (pintype "passive"))
    )
    (net (code "75") (name "unconnected-(U3-DCD-Pad1)") (class "Default")
      (node (ref "U3") (pin "1") (pinfunction "DCD_1") (pintype "passive"))
    )
    (net (code "76") (name "unconnected-(U3-DSR-Pad27)") (class "Default")
      (node (ref "U3") (pin "27") (pinfunction "DSR_27") (pintype "passive"))
    )
    (net (code "77") (name "unconnected-(U3-NC-Pad10)") (class "Default")
      (node (ref "U3") (pin "10") (pinfunction "NC_10") (pintype "passive"))
    )
    (net (code "78") (name "unconnected-(U3-NC-Pad13)") (class "Default")
      (node (ref "U3") (pin "13") (pinfunction "NC_13") (pintype "passive"))
    )
    (net (code "79") (name "unconnected-(U3-NC-Pad14)") (class "Default")
      (node (ref "U3") (pin "14") (pinfunction "NC_14") (pintype "passive"))
    )
    (net (code "80") (name "unconnected-(U3-NC-Pad15)") (class "Default")
      (node (ref "U3") (pin "15") (pinfunction "NC_15") (pintype "passive"))
    )
    (net (code "81") (name "unconnected-(U3-NC-Pad16)") (class "Default")
      (node (ref "U3") (pin "16") (pinfunction "NC_16") (pintype "passive"))
    )
    (net (code "82") (name "unconnected-(U3-NC-Pad17)") (class "Default")
      (node (ref "U3") (pin "17") (pinfunction "NC_17") (pintype "passive"))
    )
    (net (code "83") (name "unconnected-(U3-NC-Pad19)") (class "Default")
      (node (ref "U3") (pin "19") (pinfunction "NC_19") (pintype "passive"))
    )
    (net (code "84") (name "unconnected-(U3-NC-Pad20)") (class "Default")
      (node (ref "U3") (pin "20") (pinfunction "NC_20") (pintype "passive"))
    )
    (net (code "85") (name "unconnected-(U3-NC-Pad21)") (class "Default")
      (node (ref "U3") (pin "21") (pinfunction "NC_21") (pintype "passive"))
    )
    (net (code "86") (name "unconnected-(U3-NC-Pad22)") (class "Default")
      (node (ref "U3") (pin "22") (pinfunction "NC_22") (pintype "passive"))
    )
    (net (code "87") (name "unconnected-(U3-NC_{slash}_VPP-Pad18)") (class "Default")
      (node (ref "U3") (pin "18") (pinfunction "NC_/_VPP_18") (pintype "power_in"))
    )
    (net (code "88") (name "unconnected-(U3-RI-Pad2)") (class "Default")
      (node (ref "U3") (pin "2") (pinfunction "RI_2") (pintype "passive"))
    )
    (net (code "89") (name "unconnected-(U3-SUSPEND-Pad11)") (class "Default")
      (node (ref "U3") (pin "11") (pinfunction "SUSPEND_11") (pintype "output"))
    )
    (net (code "90") (name "unconnected-(U3-SUSPEND-Pad12)") (class "Default")
      (node (ref "U3") (pin "12") (pinfunction "SUSPEND_12") (pintype "output"))
    )
  )
)
